# Schematic_Rev1.net
KiCad netlist of a schematic drawn in Altium Designer
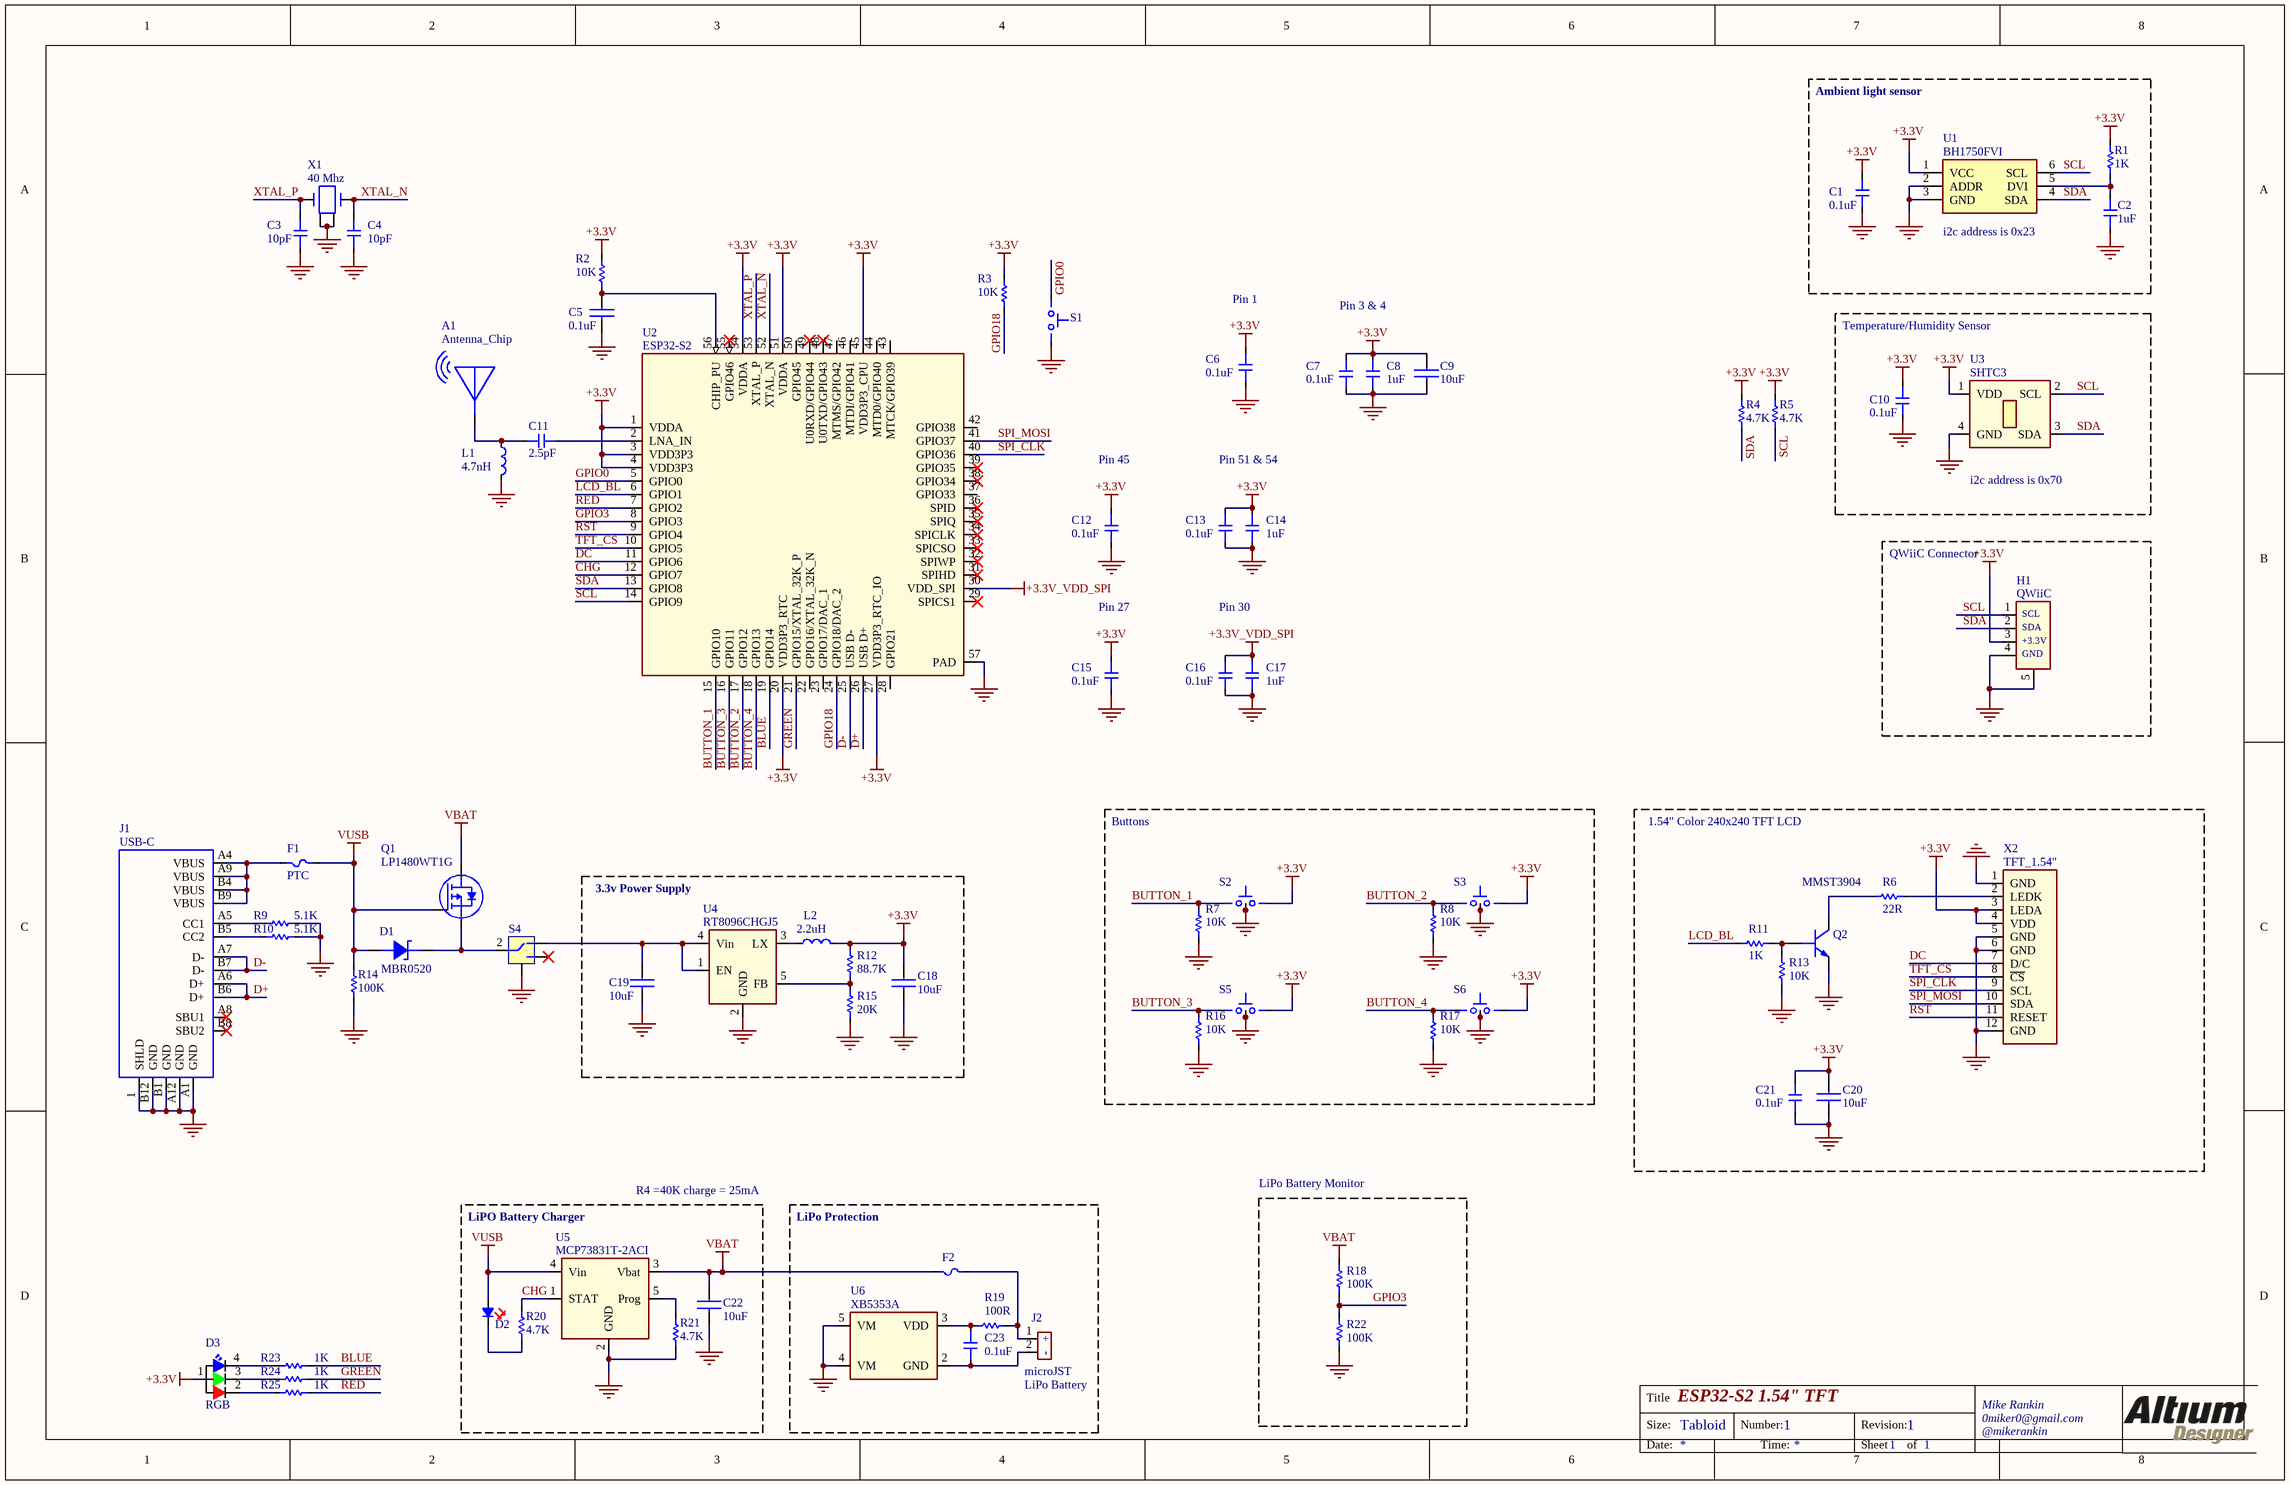
[diagram p0: Schematic_Rev1.SchDoc]

(export (version "E")
  (design (tool "Eeschema 10.0.6"))
  (components
    (comp (ref "A1")
      (value "Antenna_Chip")
      (footprint "AN9520-245")
      (description "Antenna Chip 2.4Gig")
      (fields (field (name "MANUFACTURER") "Rainsun") (field (name "LCSC_PART_NUMBER") "C99665"))
      (libsource (lib "MAR") (part "Antenna_Chip"))
    )
    (comp (ref "C1")
      (value "0.1uF")
      (footprint "CAPC0603X56N")
      (description "CAP 0.1uF 0201")
      (libsource (lib "MAR") (part "CAP_0201"))
    )
    (comp (ref "C2")
      (value "1uF")
      (footprint "CAPC1005X56N")
      (description "CAP 1uF 0402")
      (libsource (lib "MAR") (part "CAP_0402"))
    )
    (comp (ref "C3")
      (value "10pF")
      (footprint "CAPC1005X56N")
      (description "CAP 10pF 0402")
      (libsource (lib "MAR") (part "CAP_0402"))
    )
    (comp (ref "C4")
      (value "10pF")
      (footprint "CAPC1005X56N")
      (description "CAP 10pF 0402")
      (libsource (lib "MAR") (part "CAP_0402"))
    )
    (comp (ref "C5")
      (value "0.1uF")
      (footprint "CAPC1005X56N")
      (description "CAP 0.1uF 0402")
      (fields (field (name "LCSC_PART_NUMBER") "C344190") (field (name "MANUFACTURER") "CCTC"))
      (libsource (lib "") (part "CAP_0402_1"))
    )
    (comp (ref "C6")
      (value "0.1uF")
      (footprint "CAPC1005X56N")
      (description "CAP 0.1uF 0402")
      (libsource (lib "MAR") (part "CAP_0402"))
    )
    (comp (ref "C7")
      (value "0.1uF")
      (footprint "CAPC1005X56N")
      (description "CAP 0.1uF 0402")
      (libsource (lib "MAR") (part "CAP_0402"))
    )
    (comp (ref "C8")
      (value "1uF")
      (footprint "CAPC1005X56N")
      (description "CAP 1uF 0402")
      (libsource (lib "MAR") (part "CAP_0402"))
    )
    (comp (ref "C9")
      (value "10uF")
      (footprint "CAPC2012X140N")
      (description "CAP 10uF 0805")
      (libsource (lib "MAR") (part "CAP_0805"))
    )
    (comp (ref "C10")
      (value "0.1uF")
      (footprint "CAPC0603X56N")
      (description "CAP 0.1uF 0201")
      (libsource (lib "MAR") (part "CAP_0201"))
    )
    (comp (ref "C11")
      (value "2.5pF")
      (footprint "CAPC1005X56N")
      (description "CAP 2.5pF 0402")
      (libsource (lib "MAR") (part "CAP_0402"))
    )
    (comp (ref "C12")
      (value "0.1uF")
      (footprint "CAPC1005X56N")
      (description "CAP 0.1uF 0402")
      (libsource (lib "MAR") (part "CAP_0402"))
    )
    (comp (ref "C13")
      (value "0.1uF")
      (footprint "CAPC1005X56N")
      (description "CAP 0.1uF 0402")
      (libsource (lib "MAR") (part "CAP_0402"))
    )
    (comp (ref "C14")
      (value "1uF")
      (footprint "CAPC1005X56N")
      (description "CAP 1uF 0402")
      (libsource (lib "MAR") (part "CAP_0402"))
    )
    (comp (ref "C15")
      (value "0.1uF")
      (footprint "CAPC1005X56N")
      (description "CAP 0.1uF 0402")
      (libsource (lib "MAR") (part "CAP_0402"))
    )
    (comp (ref "C16")
      (value "0.1uF")
      (footprint "CAPC1005X56N")
      (description "CAP 0.1uF 0402")
      (libsource (lib "MAR") (part "CAP_0402"))
    )
    (comp (ref "C17")
      (value "1uF")
      (footprint "CAPC1005X56N")
      (description "CAP 0.1uF 0402")
      (libsource (lib "MAR") (part "CAP_0402"))
    )
    (comp (ref "C18")
      (value "10uF")
      (footprint "CAPC2012X140N")
      (description "CAP 10uF 0805")
      (libsource (lib "MAR") (part "CAP_0805"))
    )
    (comp (ref "C19")
      (value "10uF")
      (footprint "CAPC2012X140N")
      (description "CAP 10uF 0805")
      (libsource (lib "MAR") (part "CAP_0805"))
    )
    (comp (ref "C20")
      (value "10uF")
      (footprint "CAPC2012X140N")
      (description "CAP 10uF 0805")
      (fields (field (name "MANUFACTURER") "Samsung") (field (name "LCSC_PART_NUMBER") "C307520"))
      (libsource (lib "MAR") (part "CAP_0805"))
    )
    (comp (ref "C21")
      (value "0.1uF")
      (footprint "CAPC1005X56N")
      (description "CAP 0.1uF 0402")
      (libsource (lib "MAR") (part "CAP_0402"))
    )
    (comp (ref "C22")
      (value "10uF")
      (footprint "CAPC2012X140N")
      (description "CAP 10uF 0805")
      (fields (field (name "PARTNUMBER") "C307520") (field (name "MANUFACTURER") "Samsung"))
      (libsource (lib "MAR") (part "CAP_0805"))
    )
    (comp (ref "C23")
      (value "0.1uF")
      (footprint "CAPC1005X56N")
      (description "CAP 0.1uF 0402")
      (libsource (lib "MAR") (part "CAP_0402"))
    )
    (comp (ref "D1")
      (value "MBR0520")
      (footprint "SOD123")
      (description "DIODE SCHOTTKY 20V 500MA SOD123")
      (fields (field (name "MANUFACTURER") "CJ") (field (name "LCSC_PART_NUMBER") "C475717"))
      (libsource (lib "MAR") (part "MBR0520-TP"))
    )
    (comp (ref "D2")
      (value "Red Led")
      (footprint "LED1005X40N-Red")
      (description "LED Red 0402")
      (fields (field (name "PART_NUMBER") "C364556") (field (name "MANUFACTURER") "Lite-On"))
      (libsource (lib "MAR") (part "LED_0402_SMALL_Red"))
    )
    (comp (ref "D3")
      (value "RGB")
      (footprint "FC-B1010RGBT-HG")
      (description "LED,RGB LED,SMD,RoHS")
      (fields (field (name "LCSC_PART_NUMBER") "C158099") (field (name "MANUFACTURER") "Foshan"))
      (libsource (lib "MAR") (part "FC-B1010RGBT-HG"))
    )
    (comp (ref "F1")
      (value "TLC-PSMD050")
      (footprint "PTC2012X70L")
      (description "PTC FUSE 500mA hold, 1A trip 0805 SMD")
      (fields (field (name "MANUFACTURER") "TLC") (field (name "LCSC_PART_NUMBER") "C261942"))
      (libsource (lib "MAR") (part "PTC_FUSE"))
    )
    (comp (ref "F2")
      (value "TLC-PSMD050")
      (footprint "PTC2012X70L")
      (description "PTC FUSE 500mA hold, 1A trip 0805 SMD")
      (fields (field (name "MANUFACTURER") "TLC") (field (name "LCSC_PART_NUMBER") "C261942"))
      (libsource (lib "MAR") (part "PTC_FUSE"))
    )
    (comp (ref "H1")
      (value "QWiiC")
      (footprint "SM04B-SRSS-TB")
      (description "CONN HEADER 4POS .100 R/A QWIIC")
      (fields (field (name "MANUFACTURER") "JST") (field (name "PARTNUMBER") "SM04B-SRSS-TB(LF)(SN)"))
      (libsource (lib "MAR") (part "SM04B-SRSS-TB"))
    )
    (comp (ref "J1")
      (value "USB-C")
      (footprint "TYPE-C-31-M-12")
      (description "CONN RECPT USB-C")
      (fields (field (name "MANUFACTURER") "KHE") (field (name "PART_NUMBER") "C165948"))
      (libsource (lib "MAR") (part "USB-C"))
    )
    (comp (ref "J2")
      (value "CON2")
      (footprint "JST_Micro_2PIN")
      (description "JST MIcro CONN 2POS")
      (libsource (lib "MAR") (part "JST_Micro_CONN_2PIN"))
    )
    (comp (ref "L1")
      (value "4.7nH")
      (footprint "INDC1005X40L")
      (description "Inductor 4.7nH 0402")
      (libsource (lib "MAR") (part "Inductor"))
    )
    (comp (ref "L2")
      (value "2.2uH")
      (footprint "IND_2mmx2mm")
      (description "Inductor")
      (libsource (lib "MAR") (part "Inductor"))
    )
    (comp (ref "Q1")
      (value "LP1480WT1G")
      (footprint "SC-70")
      (description "MOSFET P-CH 20V 1.4A SC-70")
      (fields (field (name "MANUFACTURER") "LRC") (field (name "LCSC_PART_NUMBER") "C172434"))
      (libsource (lib "MAR") (part "LP1480WT1G"))
    )
    (comp (ref "Q2")
      (value "MMST3904")
      (footprint "SC-70")
      (description "TRANSISTOR NPN GP 40V SC-70")
      (fields (field (name "MANUFACTURER") "Changjiang") (field (name "LCSC_PART_NUMBER") "C54879"))
      (libsource (lib "MAR") (part "MMST3904"))
    )
    (comp (ref "R1")
      (value "1K")
      (footprint "RESC1005X40L (0402 FOOTPRINT)")
      (description "RES 1K 0402")
      (libsource (lib "MAR") (part "RES_0402"))
    )
    (comp (ref "R2")
      (value "10K")
      (footprint "RESC1005X40L (0402 FOOTPRINT)")
      (description "RES 10K 0402")
      (fields (field (name "LCSC_PART_NUMBER") "C258091") (field (name "MANUFACTURER") "Guangdong"))
      (libsource (lib "MAR") (part "RES_0402"))
    )
    (comp (ref "R3")
      (value "10K")
      (footprint "RESC1005X40L (0402 FOOTPRINT)")
      (description "RES 10K 0402")
      (fields (field (name "LCSC_PART_NUMBER") "C258091") (field (name "MANUFACTURER") "Guangdong"))
      (libsource (lib "MAR") (part "RES_0402"))
    )
    (comp (ref "R4")
      (value "4.7K")
      (footprint "RESC1005X40L (0402 FOOTPRINT)")
      (description "RES 4.7K 0402")
      (fields (field (name "MANUFACTURER") "Uni-Royal") (field (name "LCSC_PART_NUMBER") "C25900"))
      (libsource (lib "MAR") (part "RES_0402"))
    )
    (comp (ref "R5")
      (value "4.7K")
      (footprint "RESC1005X40L (0402 FOOTPRINT)")
      (description "RES 4.7K 0402")
      (fields (field (name "MANUFACTURER") "Uni-Royal") (field (name "LCSC_PART_NUMBER") "C25900"))
      (libsource (lib "MAR") (part "RES_0402"))
    )
    (comp (ref "R6")
      (value "22R")
      (footprint "RESC1005X40L (0402 FOOTPRINT)")
      (description "RES 22R 0402")
      (fields (field (name "LCSC_PART_NUMBER") "C25092") (field (name "MANUFACTURER") "Uniroyal"))
      (libsource (lib "MAR") (part "RES_0402"))
    )
    (comp (ref "R7")
      (value "10K")
      (footprint "RESC1005X40L (0402 FOOTPRINT)")
      (description "RES 10K 0402")
      (fields (field (name "LCSC_PART_NUMBER") "C258091") (field (name "MANUFACTURER") "Guangdong"))
      (libsource (lib "MAR") (part "RES_0402"))
    )
    (comp (ref "R8")
      (value "10K")
      (footprint "RESC1005X40L (0402 FOOTPRINT)")
      (description "RES 10K 0402")
      (fields (field (name "LCSC_PART_NUMBER") "C258091") (field (name "MANUFACTURER") "Guangdong"))
      (libsource (lib "MAR") (part "RES_0402"))
    )
    (comp (ref "R9")
      (value "5.1K")
      (footprint "RESC1005X40L (0402 FOOTPRINT)")
      (description "RES 5.1K 0402")
      (libsource (lib "MAR") (part "RES_0402"))
    )
    (comp (ref "R10")
      (value "5.1K")
      (footprint "RESC1005X40L (0402 FOOTPRINT)")
      (description "RES 5.1K 0402")
      (libsource (lib "MAR") (part "RES_0402"))
    )
    (comp (ref "R11")
      (value "1K")
      (footprint "RESC1005X40L (0402 FOOTPRINT)")
      (description "RES 1K 0402")
      (fields (field (name "LCSC_PART_NUMBER") "C106235") (field (name "MANUFACTURER") "Yageo"))
      (libsource (lib "MAR") (part "RES_0402"))
    )
    (comp (ref "R12")
      (value "88.7K")
      (footprint "RESC1005X40L (0402 FOOTPRINT)")
      (description "RES 88.7K 0402")
      (libsource (lib "MAR") (part "RES_0402"))
    )
    (comp (ref "R13")
      (value "10K")
      (footprint "RESC1005X40L (0402 FOOTPRINT)")
      (description "RES 10K 0402")
      (fields (field (name "LCSC_PART_NUMBER") "C258091") (field (name "MANUFACTURER") "Guangdong"))
      (libsource (lib "MAR") (part "RES_0402"))
    )
    (comp (ref "R14")
      (value "100K")
      (footprint "RESC1005X40L (0402 FOOTPRINT)")
      (description "RES 100K 0402")
      (libsource (lib "MAR") (part "RES_0402"))
    )
    (comp (ref "R15")
      (value "20K")
      (footprint "RESC1005X40L (0402 FOOTPRINT)")
      (description "RES 20K 0402")
      (libsource (lib "MAR") (part "RES_0402"))
    )
    (comp (ref "R16")
      (value "10K")
      (footprint "RESC1005X40L (0402 FOOTPRINT)")
      (description "RES 10K 0402")
      (fields (field (name "LCSC_PART_NUMBER") "C258091") (field (name "MANUFACTURER") "Guangdong"))
      (libsource (lib "MAR") (part "RES_0402"))
    )
    (comp (ref "R17")
      (value "10K")
      (footprint "RESC1005X40L (0402 FOOTPRINT)")
      (description "RES 10K 0402")
      (fields (field (name "LCSC_PART_NUMBER") "C258091") (field (name "MANUFACTURER") "Guangdong"))
      (libsource (lib "MAR") (part "RES_0402"))
    )
    (comp (ref "R18")
      (value "100K")
      (footprint "RESC1005X40L (0402 FOOTPRINT)")
      (description "RES 100K 0402")
      (fields (field (name "MANUFACTURER") "Uniroyal Elec") (field (name "LCSC_PART_NUMBER") "C25741"))
      (libsource (lib "MAR") (part "RES_0603"))
    )
    (comp (ref "R19")
      (value "100R")
      (footprint "RESC1005X40L (0402 FOOTPRINT)")
      (description "RES 100R 0402")
      (libsource (lib "MAR") (part "RES_0402"))
    )
    (comp (ref "R20")
      (value "4.7K")
      (footprint "RESC1005X40L (0402 FOOTPRINT)")
      (description "RES 4.7K 0402")
      (libsource (lib "MAR") (part "RES_0402"))
    )
    (comp (ref "R21")
      (value "4.7K")
      (footprint "RESC1005X40L (0402 FOOTPRINT)")
      (description "RES 4.7K 0402")
      (libsource (lib "MAR") (part "RES_0402"))
    )
    (comp (ref "R22")
      (value "100K")
      (footprint "RESC1005X40L (0402 FOOTPRINT)")
      (description "RES 100K 0402")
      (fields (field (name "MANUFACTURER") "Uniroyal Elec") (field (name "LCSC_PART_NUMBER") "C25741"))
      (libsource (lib "MAR") (part "RES_0603"))
    )
    (comp (ref "R23")
      (value "1K")
      (footprint "RESC1005X40L (0402 FOOTPRINT)")
      (description "RES 1K 0402")
      (fields (field (name "LCSC_PART_NUMBER") "C106235") (field (name "MANUFACTURER") "Yageo"))
      (libsource (lib "MAR") (part "RES_0402"))
    )
    (comp (ref "R24")
      (value "1K")
      (footprint "RESC1005X40L (0402 FOOTPRINT)")
      (description "RES 1K 0402")
      (fields (field (name "LCSC_PART_NUMBER") "C106235") (field (name "MANUFACTURER") "Yageo"))
      (libsource (lib "MAR") (part "RES_0402"))
    )
    (comp (ref "R25")
      (value "1K")
      (footprint "RESC1005X40L (0402 FOOTPRINT)")
      (description "RES 1K 0402")
      (fields (field (name "LCSC_PART_NUMBER") "C106235") (field (name "MANUFACTURER") "Yageo"))
      (libsource (lib "MAR") (part "RES_0402"))
    )
    (comp (ref "S1")
      (value "~")
      (footprint "TS-1088R-02526")
      (description "Tactile Micro Switch")
      (fields (field (name "PART_NUMBER") "C455281") (field (name "MANUFACTURER") "XUNPU"))
      (libsource (lib "MAR") (part "TS-1088R-02526"))
    )
    (comp (ref "S2")
      (value "Push")
      (footprint "122514")
      (description "Side Actuated Button R/A")
      (fields (field (name "LCSC_PART_NUMBER") "C319377") (field (name "MANUFACTURER") "HYP"))
      (libsource (lib "MAR") (part "Side Actuated Button R/A"))
    )
    (comp (ref "S3")
      (value "Push")
      (footprint "122514")
      (description "Side Actuated Button R/A")
      (fields (field (name "LCSC_PART_NUMBER") "C319377") (field (name "MANUFACTURER") "HYP"))
      (libsource (lib "MAR") (part "Side Actuated Button R/A"))
    )
    (comp (ref "S4")
      (value "SWITCH SLIDE")
      (footprint "K3-1296S-E1")
      (description "SWITCH SLIDE SMD")
      (fields
        (field (name "MANUFACTURER") "Korean Hroparts Elec")
        (field (name "LCSC_PART_NUMBER") "C128955")
      )
      (libsource (lib "MAR") (part "K3-1296S-E1"))
    )
    (comp (ref "S5")
      (value "Push")
      (footprint "122514")
      (description "Side Actuated Button R/A")
      (fields (field (name "LCSC_PART_NUMBER") "C319377") (field (name "MANUFACTURER") "HYP"))
      (libsource (lib "MAR") (part "Side Actuated Button R/A"))
    )
    (comp (ref "S6")
      (value "Push")
      (footprint "122514")
      (description "Side Actuated Button R/A")
      (fields (field (name "LCSC_PART_NUMBER") "C319377") (field (name "MANUFACTURER") "HYP"))
      (libsource (lib "MAR") (part "Side Actuated Button R/A"))
    )
    (comp (ref "U1")
      (value "BH1750FVI")
      (footprint "WSOF-6")
      (description "Optical Sensor Ambient I2C 6-SMD")
      (fields (field (name "MANUFACTURER") "Rohm") (field (name "PART_NUMBER") "C78960"))
      (libsource (lib "MAR") (part "BH1750FVI"))
    )
    (comp (ref "U2")
      (value "ESP32-S2")
      (footprint "QFN56_0.4mm pitch")
      (description "WIFI/Bluetooth, QFN-56 7x7")
      (fields (field (name "MANUFACTURER") "Espressif") (field (name "PART_NUMBER") "C529594"))
      (libsource (lib "MAR") (part "ESP32-S2"))
    )
    (comp (ref "U3")
      (value "SHTC3")
      (footprint "DFN-4 (2.0mm X 2.0mm)")
      (description "Humidity/Temperature Sensor")
      (fields (field (name "MANUFACTURER") "Sensirion") (field (name "PART_NUMBER") "SHTC3"))
      (libsource (lib "MAR") (part "SHTC3"))
    )
    (comp (ref "U4")
      (value "RT8096CHGJ5")
      (footprint "SOT95P280X144-5N")
      (description "IC DC SWITCHING REG 1A SOT23-5")
      (fields (field (name "MANUFACTURER") "Richtek") (field (name "PARTNUMBER") "RT8096CHGJ5"))
      (libsource (lib "MAR") (part "RT8096CHGJ5"))
    )
    (comp (ref "U5")
      (value "MCP73831T-2ACI")
      (footprint "SOT95P280X144-5N")
      (description "Charger IC Lithium-Ion/Polymer SOT23-5")
      (fields (field (name "MANUFACTURER") "Microchip") (field (name "MAN_PART_NUMBER") "MCP73831T-2ACI/OT"))
      (libsource (lib "MAR") (part "MCP73831T-2ACI/OT"))
    )
    (comp (ref "U6")
      (value "XB5353A")
      (footprint "SOT95P280X144-5N")
      (description "IC Battery Protection")
      (fields (field (name "MANUFACTURER") "XySemi") (field (name "LCSC_PART_NUMBER") "C80628"))
      (libsource (lib "MAR") (part "XB5353A"))
    )
    (comp (ref "X1")
      (value "40 Mhz")
      (footprint "OSC20X16")
      (description "CRYSTAL 40MHZ 10PF SMD")
      (fields (field (name "PART_NUMBER") "ECS-400-10-37B2-CKM") (field (name "MANUFACTURER") "ECS"))
      (libsource (lib "MAR") (part "40Mhz"))
    )
    (comp (ref "X2")
      (value "TFT_1.54\"")
      (footprint "TFT_GLASS 1.54 INCH")
      (description "1.54 INCH TFT GLASS COLOR")
      (fields (field (name "MAN_PART_NUMBER") "ER-TFT1.54-1") (field (name "MANUFACTURER") "BuyDisplay"))
      (libsource (lib "MAR") (part "TFT_GLASS 1.54 INCH COLOR"))
    )
  )
  (nets
    (net (code "1") (name "+3.3V") (class "Default")
      (node (ref "C1") (pin "1") (pintype "passive"))
      (node (ref "C10") (pin "1") (pintype "passive"))
      (node (ref "C12") (pin "1") (pintype "passive"))
      (node (ref "C13") (pin "1") (pintype "passive"))
      (node (ref "C14") (pin "1") (pintype "passive"))
      (node (ref "C15") (pin "1") (pintype "passive"))
      (node (ref "C18") (pin "1") (pinfunction "1_1") (pintype "passive"))
      (node (ref "C20") (pin "1") (pinfunction "1_1") (pintype "passive"))
      (node (ref "C21") (pin "1") (pintype "passive"))
      (node (ref "C6") (pin "1") (pintype "passive"))
      (node (ref "C7") (pin "1") (pintype "passive"))
      (node (ref "C8") (pin "1") (pintype "passive"))
      (node (ref "C9") (pin "1") (pinfunction "1_1") (pintype "passive"))
      (node (ref "D3") (pin "1") (pintype "passive"))
      (node (ref "H1") (pin "3") (pintype "passive"))
      (node (ref "L2") (pin "2") (pinfunction "2_2") (pintype "passive"))
      (node (ref "R1") (pin "1") (pintype "passive"))
      (node (ref "R12") (pin "2") (pintype "passive"))
      (node (ref "R2") (pin "1") (pintype "passive"))
      (node (ref "R3") (pin "1") (pintype "passive"))
      (node (ref "R4") (pin "2") (pintype "passive"))
      (node (ref "R5") (pin "2") (pintype "passive"))
      (node (ref "S2") (pin "2") (pinfunction "B_2") (pintype "passive"))
      (node (ref "S3") (pin "2") (pinfunction "B_2") (pintype "passive"))
      (node (ref "S5") (pin "2") (pinfunction "B_2") (pintype "passive"))
      (node (ref "S6") (pin "2") (pinfunction "B_2") (pintype "passive"))
      (node (ref "U1") (pin "1") (pinfunction "VCC_1") (pintype "power_in"))
      (node (ref "U2") (pin "1") (pinfunction "VDDA_1") (pintype "power_in"))
      (node (ref "U2") (pin "20") (pinfunction "VDD3P3_RTC_20") (pintype "power_in"))
      (node (ref "U2") (pin "27") (pinfunction "VDD3P3_RTC_IO_27") (pintype "power_in"))
      (node (ref "U2") (pin "3") (pinfunction "VDD3P3_3") (pintype "power_in"))
      (node (ref "U2") (pin "4") (pinfunction "VDD3P3_4") (pintype "power_in"))
      (node (ref "U2") (pin "45") (pinfunction "VDD3P3_CPU_45") (pintype "power_in"))
      (node (ref "U2") (pin "51") (pinfunction "VDDA_51") (pintype "power_in"))
      (node (ref "U2") (pin "54") (pinfunction "VDDA_54") (pintype "power_in"))
      (node (ref "U3") (pin "1") (pinfunction "VDD_1") (pintype "power_in"))
      (node (ref "X2") (pin "3") (pinfunction "LEDA_3") (pintype "passive"))
      (node (ref "X2") (pin "4") (pinfunction "VDD_4") (pintype "power_in"))
    )
    (net (code "2") (name "+3.3V_VDD_SPI") (class "Default")
      (node (ref "C16") (pin "1") (pintype "passive"))
      (node (ref "C17") (pin "1") (pintype "passive"))
      (node (ref "U2") (pin "30") (pinfunction "VDD_SPI_30") (pintype "power_in"))
    )
    (net (code "3") (name "/BLUE") (class "Default")
      (node (ref "R23") (pin "2") (pintype "passive"))
      (node (ref "U2") (pin "19") (pinfunction "GPIO14_19") (pintype "passive"))
    )
    (net (code "4") (name "/BUTTON_1") (class "Default")
      (node (ref "R7") (pin "1") (pintype "passive"))
      (node (ref "S2") (pin "1") (pinfunction "A_1") (pintype "passive"))
      (node (ref "U2") (pin "15") (pinfunction "GPIO10_15") (pintype "passive"))
    )
    (net (code "5") (name "/BUTTON_2") (class "Default")
      (node (ref "R8") (pin "1") (pintype "passive"))
      (node (ref "S3") (pin "1") (pinfunction "A_1") (pintype "passive"))
      (node (ref "U2") (pin "17") (pinfunction "GPIO12_17") (pintype "passive"))
    )
    (net (code "6") (name "/BUTTON_3") (class "Default")
      (node (ref "R16") (pin "1") (pintype "passive"))
      (node (ref "S5") (pin "1") (pinfunction "A_1") (pintype "passive"))
      (node (ref "U2") (pin "16") (pinfunction "GPIO11_16") (pintype "passive"))
    )
    (net (code "7") (name "/BUTTON_4") (class "Default")
      (node (ref "R17") (pin "1") (pintype "passive"))
      (node (ref "S6") (pin "1") (pinfunction "A_1") (pintype "passive"))
      (node (ref "U2") (pin "18") (pinfunction "GPIO13_18") (pintype "passive"))
    )
    (net (code "8") (name "/CHG") (class "Default")
      (node (ref "R20") (pin "1") (pintype "passive"))
      (node (ref "U2") (pin "12") (pinfunction "GPIO7_12") (pintype "passive"))
      (node (ref "U5") (pin "1") (pinfunction "STAT_1") (pintype "passive"))
    )
    (net (code "9") (name "/D+") (class "Default")
      (node (ref "J1") (pin "A6") (pinfunction "D+_A6") (pintype "power_in"))
      (node (ref "J1") (pin "B6") (pinfunction "D+_B6") (pintype "power_in"))
      (node (ref "U2") (pin "26") (pinfunction "USB_D+_26") (pintype "passive"))
    )
    (net (code "10") (name "/D-") (class "Default")
      (node (ref "J1") (pin "A7") (pinfunction "D-_A7") (pintype "power_in"))
      (node (ref "J1") (pin "B7") (pinfunction "D-_B7") (pintype "power_in"))
      (node (ref "U2") (pin "25") (pinfunction "USB_D-_25") (pintype "passive"))
    )
    (net (code "11") (name "/DC") (class "Default")
      (node (ref "U2") (pin "11") (pinfunction "GPIO6_11") (pintype "passive"))
      (node (ref "X2") (pin "7") (pinfunction "D/C_7") (pintype "passive"))
    )
    (net (code "12") (name "/GPIO0") (class "Default")
      (node (ref "S1") (pin "1") (pinfunction "A_1") (pintype "passive"))
      (node (ref "U2") (pin "5") (pinfunction "GPIO0_5") (pintype "passive"))
    )
    (net (code "13") (name "/GPIO3") (class "Default")
      (node (ref "R18") (pin "2") (pintype "passive"))
      (node (ref "R22") (pin "1") (pintype "passive"))
      (node (ref "U2") (pin "8") (pinfunction "GPIO3_8") (pintype "passive"))
    )
    (net (code "14") (name "/GPIO18") (class "Default")
      (node (ref "R3") (pin "2") (pintype "passive"))
      (node (ref "U2") (pin "24") (pinfunction "GPIO18/DAC_2_24") (pintype "passive"))
    )
    (net (code "15") (name "/GREEN") (class "Default")
      (node (ref "R24") (pin "2") (pintype "passive"))
      (node (ref "U2") (pin "21") (pinfunction "GPIO15/XTAL_32K_P_21") (pintype "passive"))
    )
    (net (code "16") (name "/LCD_BL") (class "Default")
      (node (ref "R11") (pin "1") (pintype "passive"))
      (node (ref "U2") (pin "6") (pinfunction "GPIO1_6") (pintype "passive"))
    )
    (net (code "17") (name "/RED") (class "Default")
      (node (ref "R25") (pin "2") (pintype "passive"))
      (node (ref "U2") (pin "7") (pinfunction "GPIO2_7") (pintype "passive"))
    )
    (net (code "18") (name "/RST") (class "Default")
      (node (ref "U2") (pin "9") (pinfunction "GPIO4_9") (pintype "passive"))
      (node (ref "X2") (pin "11") (pinfunction "RESET_11") (pintype "passive"))
    )
    (net (code "19") (name "/SCL") (class "Default")
      (node (ref "H1") (pin "1") (pintype "passive"))
      (node (ref "R5") (pin "1") (pintype "passive"))
      (node (ref "U1") (pin "6") (pinfunction "SCL_6") (pintype "passive"))
      (node (ref "U2") (pin "14") (pinfunction "GPIO9_14") (pintype "passive"))
      (node (ref "U3") (pin "2") (pinfunction "SCL_2") (pintype "passive"))
    )
    (net (code "20") (name "/SDA") (class "Default")
      (node (ref "H1") (pin "2") (pintype "passive"))
      (node (ref "R4") (pin "1") (pintype "passive"))
      (node (ref "U1") (pin "4") (pinfunction "SDA_4") (pintype "passive"))
      (node (ref "U2") (pin "13") (pinfunction "GPIO8_13") (pintype "passive"))
      (node (ref "U3") (pin "3") (pinfunction "SDA_3") (pintype "passive"))
    )
    (net (code "21") (name "/SPI_CLK") (class "Default")
      (node (ref "U2") (pin "40") (pinfunction "GPIO36_40") (pintype "passive"))
      (node (ref "X2") (pin "9") (pinfunction "SCL_9") (pintype "passive"))
    )
    (net (code "22") (name "/SPI_MOSI") (class "Default")
      (node (ref "U2") (pin "41") (pinfunction "GPIO37_41") (pintype "passive"))
      (node (ref "X2") (pin "10") (pinfunction "SDA_10") (pintype "passive"))
    )
    (net (code "23") (name "/TFT_CS") (class "Default")
      (node (ref "U2") (pin "10") (pinfunction "GPIO5_10") (pintype "passive"))
      (node (ref "X2") (pin "8") (pinfunction "~{CS}_8") (pintype "passive"))
    )
    (net (code "24") (name "/XTAL_N") (class "Default")
      (node (ref "C4") (pin "1") (pintype "passive"))
      (node (ref "U2") (pin "52") (pinfunction "XTAL_N_52") (pintype "passive"))
      (node (ref "X1") (pin "3") (pinfunction "3_3") (pintype "passive"))
    )
    (net (code "25") (name "/XTAL_P") (class "Default")
      (node (ref "C3") (pin "1") (pintype "passive"))
      (node (ref "U2") (pin "53") (pinfunction "XTAL_P_53") (pintype "passive"))
      (node (ref "X1") (pin "1") (pinfunction "1_1") (pintype "passive"))
    )
    (net (code "26") (name "GND") (class "Default")
      (node (ref "C1") (pin "2") (pintype "passive"))
      (node (ref "C10") (pin "2") (pintype "passive"))
      (node (ref "C12") (pin "2") (pintype "passive"))
      (node (ref "C13") (pin "2") (pintype "passive"))
      (node (ref "C14") (pin "2") (pintype "passive"))
      (node (ref "C15") (pin "2") (pintype "passive"))
      (node (ref "C16") (pin "2") (pintype "passive"))
      (node (ref "C17") (pin "2") (pintype "passive"))
      (node (ref "C18") (pin "2") (pinfunction "2_2") (pintype "passive"))
      (node (ref "C19") (pin "2") (pinfunction "2_2") (pintype "passive"))
      (node (ref "C2") (pin "2") (pintype "passive"))
      (node (ref "C20") (pin "2") (pinfunction "2_2") (pintype "passive"))
      (node (ref "C21") (pin "2") (pintype "passive"))
      (node (ref "C22") (pin "2") (pinfunction "2_2") (pintype "passive"))
      (node (ref "C3") (pin "2") (pintype "passive"))
      (node (ref "C4") (pin "2") (pintype "passive"))
      (node (ref "C5") (pin "2") (pinfunction "2_2") (pintype "passive"))
      (node (ref "C6") (pin "2") (pintype "passive"))
      (node (ref "C7") (pin "2") (pintype "passive"))
      (node (ref "C8") (pin "2") (pintype "passive"))
      (node (ref "C9") (pin "2") (pinfunction "2_2") (pintype "passive"))
      (node (ref "H1") (pin "4") (pintype "passive"))
      (node (ref "H1") (pin "5") (pintype "passive"))
      (node (ref "J1") (pin "1") (pinfunction "SHLD_1") (pintype "power_in"))
      (node (ref "J1") (pin "A1") (pinfunction "GND_A1") (pintype "power_in"))
      (node (ref "J1") (pin "A12") (pinfunction "GND_A12") (pintype "power_in"))
      (node (ref "J1") (pin "B1") (pinfunction "GND_B1") (pintype "power_in"))
      (node (ref "J1") (pin "B12") (pinfunction "GND_B12") (pintype "passive"))
      (node (ref "L1") (pin "2") (pinfunction "2_2") (pintype "passive"))
      (node (ref "Q2") (pin "2") (pinfunction "E_2") (pintype "passive"))
      (node (ref "R10") (pin "1") (pintype "passive"))
      (node (ref "R13") (pin "2") (pintype "passive"))
      (node (ref "R14") (pin "2") (pintype "passive"))
      (node (ref "R15") (pin "1") (pintype "passive"))
      (node (ref "R16") (pin "2") (pintype "passive"))
      (node (ref "R17") (pin "2") (pintype "passive"))
      (node (ref "R21") (pin "2") (pintype "passive"))
      (node (ref "R22") (pin "2") (pintype "passive"))
      (node (ref "R7") (pin "2") (pintype "passive"))
      (node (ref "R8") (pin "2") (pintype "passive"))
      (node (ref "R9") (pin "1") (pintype "passive"))
      (node (ref "S1") (pin "2") (pinfunction "B_2") (pintype "passive"))
      (node (ref "S2") (pin "3") (pinfunction "3_3") (pintype "passive"))
      (node (ref "S2") (pin "4") (pinfunction "4_4") (pintype "passive"))
      (node (ref "S3") (pin "3") (pinfunction "3_3") (pintype "passive"))
      (node (ref "S3") (pin "4") (pinfunction "4_4") (pintype "passive"))
      (node (ref "S4") (pin "4") (pinfunction "4_4") (pintype "passive"))
      (node (ref "S5") (pin "3") (pinfunction "3_3") (pintype "passive"))
      (node (ref "S5") (pin "4") (pinfunction "4_4") (pintype "passive"))
      (node (ref "S6") (pin "3") (pinfunction "3_3") (pintype "passive"))
      (node (ref "S6") (pin "4") (pinfunction "4_4") (pintype "passive"))
      (node (ref "U1") (pin "2") (pinfunction "ADDR_2") (pintype "passive"))
      (node (ref "U1") (pin "3") (pinfunction "GND_3") (pintype "power_in"))
      (node (ref "U2") (pin "57") (pinfunction "PAD_57") (pintype "power_in"))
      (node (ref "U3") (pin "4") (pinfunction "GND_4") (pintype "power_in"))
      (node (ref "U4") (pin "2") (pinfunction "GND_2") (pintype "power_in"))
      (node (ref "U5") (pin "2") (pinfunction "GND_2") (pintype "power_in"))
      (node (ref "U6") (pin "4") (pinfunction "VM_4") (pintype "passive"))
      (node (ref "U6") (pin "5") (pinfunction "VM_5") (pintype "passive"))
      (node (ref "X1") (pin "2") (pinfunction "2_2") (pintype "power_in"))
      (node (ref "X1") (pin "4") (pinfunction "4_4") (pintype "power_in"))
      (node (ref "X2") (pin "1") (pinfunction "GND_1") (pintype "power_in"))
      (node (ref "X2") (pin "12") (pinfunction "GND_12") (pintype "power_in"))
      (node (ref "X2") (pin "5") (pinfunction "GND_5") (pintype "power_in"))
      (node (ref "X2") (pin "6") (pinfunction "GND_6") (pintype "power_in"))
    )
    (net (code "27") (name "Net-(A1-Pad1)") (class "Default")
      (node (ref "A1") (pin "1") (pintype "passive"))
      (node (ref "C11") (pin "1") (pintype "passive"))
      (node (ref "L1") (pin "1") (pinfunction "1_1") (pintype "passive"))
    )
    (net (code "28") (name "Net-(D1-Cathode)") (class "Default")
      (node (ref "D1") (pin "1") (pinfunction "Cathode_1") (pintype "passive"))
      (node (ref "Q1") (pin "2") (pinfunction "S_2") (pintype "passive"))
      (node (ref "S4") (pin "2") (pinfunction "2_2") (pintype "passive"))
    )
    (net (code "29") (name "Net-(D2-Pad1)") (class "Default")
      (node (ref "D2") (pin "1") (pintype "passive"))
      (node (ref "R20") (pin "2") (pintype "passive"))
    )
    (net (code "30") (name "Net-(D3-Pad2)") (class "Default")
      (node (ref "D3") (pin "2") (pintype "passive"))
      (node (ref "R25") (pin "1") (pintype "passive"))
    )
    (net (code "31") (name "Net-(D3-Pad3)") (class "Default")
      (node (ref "D3") (pin "3") (pintype "passive"))
      (node (ref "R24") (pin "1") (pintype "passive"))
    )
    (net (code "32") (name "Net-(D3-Pad4)") (class "Default")
      (node (ref "D3") (pin "4") (pintype "passive"))
      (node (ref "R23") (pin "1") (pintype "passive"))
    )
    (net (code "33") (name "Net-(F1-Pad2)") (class "Default")
      (node (ref "F1") (pin "2") (pintype "passive"))
      (node (ref "J1") (pin "A4") (pinfunction "VBUS_A4") (pintype "passive"))
      (node (ref "J1") (pin "A9") (pinfunction "VBUS_A9") (pintype "power_in"))
      (node (ref "J1") (pin "B4") (pinfunction "VBUS_B4") (pintype "power_in"))
      (node (ref "J1") (pin "B9") (pinfunction "VBUS_B9") (pintype "passive"))
    )
    (net (code "34") (name "Net-(F2-Pad1)") (class "Default")
      (node (ref "F2") (pin "1") (pintype "passive"))
      (node (ref "J2") (pin "1") (pintype "passive"))
      (node (ref "R19") (pin "1") (pintype "passive"))
    )
    (net (code "35") (name "Net-(J1-CC1)") (class "Default")
      (node (ref "J1") (pin "A5") (pinfunction "CC1_A5") (pintype "power_in"))
      (node (ref "R9") (pin "2") (pintype "passive"))
    )
    (net (code "36") (name "Net-(J1-CC2)") (class "Default")
      (node (ref "J1") (pin "B5") (pinfunction "CC2_B5") (pintype "power_in"))
      (node (ref "R10") (pin "2") (pintype "passive"))
    )
    (net (code "37") (name "Net-(Q2-B)") (class "Default")
      (node (ref "Q2") (pin "1") (pinfunction "B_1") (pintype "passive"))
      (node (ref "R11") (pin "2") (pintype "passive"))
      (node (ref "R13") (pin "1") (pintype "passive"))
    )
    (net (code "38") (name "Net-(Q2-C)") (class "Default")
      (node (ref "Q2") (pin "3") (pinfunction "C_3") (pintype "passive"))
      (node (ref "R6") (pin "2") (pintype "passive"))
    )
    (net (code "39") (name "Net-(U1-DVI)") (class "Default")
      (node (ref "C2") (pin "1") (pintype "passive"))
      (node (ref "R1") (pin "2") (pintype "passive"))
      (node (ref "U1") (pin "5") (pinfunction "DVI_5") (pintype "passive"))
    )
    (net (code "40") (name "Net-(U2-CHIP_PU)") (class "Default")
      (node (ref "C5") (pin "1") (pinfunction "1_1") (pintype "passive"))
      (node (ref "R2") (pin "2") (pintype "passive"))
      (node (ref "U2") (pin "56") (pinfunction "CHIP_PU_56") (pintype "input"))
    )
    (net (code "41") (name "Net-(U2-LNA_IN)") (class "Default")
      (node (ref "C11") (pin "2") (pintype "passive"))
      (node (ref "U2") (pin "2") (pinfunction "LNA_IN_2") (pintype "passive"))
    )
    (net (code "42") (name "Net-(U4-EN)") (class "Default")
      (node (ref "C19") (pin "1") (pinfunction "1_1") (pintype "passive"))
      (node (ref "S4") (pin "1") (pinfunction "1_1") (pintype "passive"))
      (node (ref "U4") (pin "1") (pinfunction "EN_1") (pintype "passive"))
      (node (ref "U4") (pin "4") (pinfunction "Vin_4") (pintype "passive"))
    )
    (net (code "43") (name "Net-(U4-FB)") (class "Default")
      (node (ref "R12") (pin "1") (pintype "passive"))
      (node (ref "R15") (pin "2") (pintype "passive"))
      (node (ref "U4") (pin "5") (pinfunction "FB_5") (pintype "passive"))
    )
    (net (code "44") (name "Net-(U4-LX)") (class "Default")
      (node (ref "L2") (pin "1") (pinfunction "1_1") (pintype "passive"))
      (node (ref "U4") (pin "3") (pinfunction "LX_3") (pintype "passive"))
    )
    (net (code "45") (name "Net-(U5-Prog)") (class "Default")
      (node (ref "R21") (pin "1") (pintype "passive"))
      (node (ref "U5") (pin "5") (pinfunction "Prog_5") (pintype "passive"))
    )
    (net (code "46") (name "Net-(U6-GND)") (class "Default")
      (node (ref "C23") (pin "2") (pintype "passive"))
      (node (ref "J2") (pin "2") (pintype "passive"))
      (node (ref "U6") (pin "2") (pinfunction "GND_2") (pintype "power_in"))
    )
    (net (code "47") (name "Net-(U6-VDD)") (class "Default")
      (node (ref "C23") (pin "1") (pintype "passive"))
      (node (ref "R19") (pin "2") (pintype "passive"))
      (node (ref "U6") (pin "3") (pinfunction "VDD_3") (pintype "power_in"))
    )
    (net (code "48") (name "Net-(X2-LEDK)") (class "Default")
      (node (ref "R6") (pin "1") (pintype "passive"))
      (node (ref "X2") (pin "2") (pinfunction "LEDK_2") (pintype "passive"))
    )
    (net (code "49") (name "VBAT") (class "Default")
      (node (ref "C22") (pin "1") (pinfunction "1_1") (pintype "passive"))
      (node (ref "F2") (pin "2") (pintype "passive"))
      (node (ref "Q1") (pin "3") (pinfunction "D_3") (pintype "passive"))
      (node (ref "R18") (pin "1") (pintype "passive"))
      (node (ref "U5") (pin "3") (pinfunction "Vbat_3") (pintype "passive"))
    )
    (net (code "50") (name "VUSB") (class "Default")
      (node (ref "D1") (pin "2") (pinfunction "Annode_2") (pintype "passive"))
      (node (ref "D2") (pin "2") (pintype "passive"))
      (node (ref "F1") (pin "1") (pintype "passive"))
      (node (ref "Q1") (pin "1") (pinfunction "G_1") (pintype "passive"))
      (node (ref "R14") (pin "1") (pintype "passive"))
      (node (ref "U5") (pin "4") (pinfunction "Vin_4") (pintype "passive"))
    )
    (net (code "51") (name "unconnected-(J1-SBU1-PadA8)") (class "Default")
      (node (ref "J1") (pin "A8") (pinfunction "SBU1_A8") (pintype "power_in+no_connect"))
    )
    (net (code "52") (name "unconnected-(J1-SBU2-PadB8)") (class "Default")
      (node (ref "J1") (pin "B8") (pinfunction "SBU2_B8") (pintype "power_in+no_connect"))
    )
    (net (code "53") (name "unconnected-(S4-Pad3)") (class "Default")
      (node (ref "S4") (pin "3") (pinfunction "3_3") (pintype "passive+no_connect"))
    )
    (net (code "54") (name "unconnected-(U2-GPIO16{slash}XTAL_32K_N-Pad22)") (class "Default")
      (node (ref "U2") (pin "22") (pinfunction "GPIO16/XTAL_32K_N_22") (pintype "passive"))
    )
    (net (code "55") (name "unconnected-(U2-GPIO17{slash}DAC_1-Pad23)") (class "Default")
      (node (ref "U2") (pin "23") (pinfunction "GPIO17/DAC_1_23") (pintype "passive"))
    )
    (net (code "56") (name "unconnected-(U2-GPIO21-Pad28)") (class "Default")
      (node (ref "U2") (pin "28") (pinfunction "GPIO21_28") (pintype "passive"))
    )
    (net (code "57") (name "unconnected-(U2-GPIO33-Pad37)") (class "Default")
      (node (ref "U2") (pin "37") (pinfunction "GPIO33_37") (pintype "passive"))
    )
    (net (code "58") (name "unconnected-(U2-GPIO34-Pad38)") (class "Default")
      (node (ref "U2") (pin "38") (pinfunction "GPIO34_38") (pintype "passive+no_connect"))
    )
    (net (code "59") (name "unconnected-(U2-GPIO35-Pad39)") (class "Default")
      (node (ref "U2") (pin "39") (pinfunction "GPIO35_39") (pintype "passive+no_connect"))
    )
    (net (code "60") (name "unconnected-(U2-GPIO38-Pad42)") (class "Default")
      (node (ref "U2") (pin "42") (pinfunction "GPIO38_42") (pintype "passive"))
    )
    (net (code "61") (name "unconnected-(U2-GPIO45-Pad50)") (class "Default")
      (node (ref "U2") (pin "50") (pinfunction "GPIO45_50") (pintype "passive"))
    )
    (net (code "62") (name "unconnected-(U2-GPIO46-Pad55)") (class "Default")
      (node (ref "U2") (pin "55") (pinfunction "GPIO46_55") (pintype "input+no_connect"))
    )
    (net (code "63") (name "unconnected-(U2-MTCK{slash}GPIO39-Pad43)") (class "Default")
      (node (ref "U2") (pin "43") (pinfunction "MTCK/GPIO39_43") (pintype "passive"))
    )
    (net (code "64") (name "unconnected-(U2-MTD0{slash}GPIO40-Pad44)") (class "Default")
      (node (ref "U2") (pin "44") (pinfunction "MTD0/GPIO40_44") (pintype "passive"))
    )
    (net (code "65") (name "unconnected-(U2-MTDI{slash}GPIO41-Pad46)") (class "Default")
      (node (ref "U2") (pin "46") (pinfunction "MTDI/GPIO41_46") (pintype "passive"))
    )
    (net (code "66") (name "unconnected-(U2-MTMS{slash}GPIO42-Pad47)") (class "Default")
      (node (ref "U2") (pin "47") (pinfunction "MTMS/GPIO42_47") (pintype "passive"))
    )
    (net (code "67") (name "unconnected-(U2-SPICLK-Pad34)") (class "Default")
      (node (ref "U2") (pin "34") (pinfunction "SPICLK_34") (pintype "passive+no_connect"))
    )
    (net (code "68") (name "unconnected-(U2-SPICS1-Pad29)") (class "Default")
      (node (ref "U2") (pin "29") (pinfunction "SPICS1_29") (pintype "passive+no_connect"))
    )
    (net (code "69") (name "unconnected-(U2-SPICSO-Pad33)") (class "Default")
      (node (ref "U2") (pin "33") (pinfunction "SPICSO_33") (pintype "passive+no_connect"))
    )
    (net (code "70") (name "unconnected-(U2-SPID-Pad36)") (class "Default")
      (node (ref "U2") (pin "36") (pinfunction "SPID_36") (pintype "passive+no_connect"))
    )
    (net (code "71") (name "unconnected-(U2-SPIHD-Pad31)") (class "Default")
      (node (ref "U2") (pin "31") (pinfunction "SPIHD_31") (pintype "passive+no_connect"))
    )
    (net (code "72") (name "unconnected-(U2-SPIQ-Pad35)") (class "Default")
      (node (ref "U2") (pin "35") (pinfunction "SPIQ_35") (pintype "passive+no_connect"))
    )
    (net (code "73") (name "unconnected-(U2-SPIWP-Pad32)") (class "Default")
      (node (ref "U2") (pin "32") (pinfunction "SPIWP_32") (pintype "passive+no_connect"))
    )
    (net (code "74") (name "unconnected-(U2-U0RXD{slash}GPIO44-Pad49)") (class "Default")
      (node (ref "U2") (pin "49") (pinfunction "U0RXD/GPIO44_49") (pintype "passive+no_connect"))
    )
    (net (code "75") (name "unconnected-(U2-U0TXD{slash}GPIO43-Pad48)") (class "Default")
      (node (ref "U2") (pin "48") (pinfunction "U0TXD/GPIO43_48") (pintype "passive+no_connect"))
    )
  )
)
